# MatrixLED_v2_SCH.net
KiCad netlist of a schematic drawn in Altium Designer
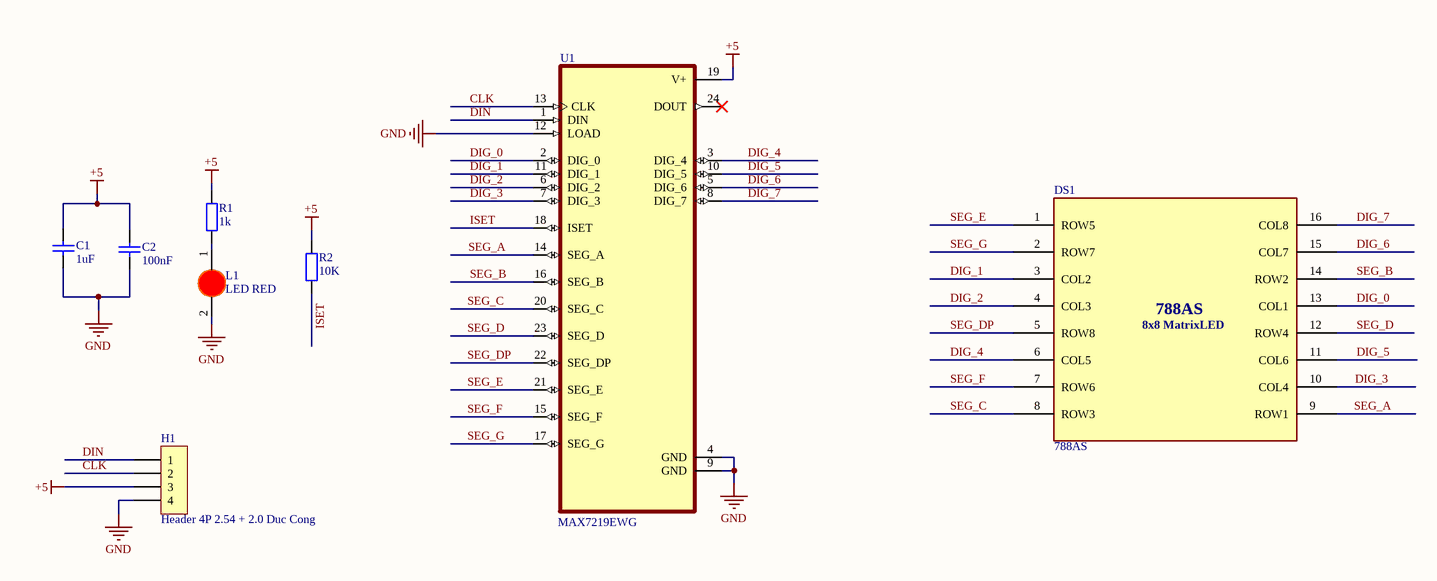
[diagram p0: MatrixLED_v2_SCH.SchDoc]

(export (version "E")
  (design (tool "Eeschema 10.0.6"))
  (components
    (comp (ref "C1")
      (value "1uF")
      (footprint "tu 0603")
      (description "Dán")
      (libsource (lib "namnt_Lib") (part "Tu 0603 104 50V 10%"))
    )
    (comp (ref "C2")
      (value "100nF")
      (footprint "tu 0603")
      (description "Dán")
      (libsource (lib "namnt_Lib") (part "Tu 0603 104 50V 10%"))
    )
    (comp (ref "DS1")
      (value "788AS")
      (footprint "788AS")
      (description "31.70mm (1.2â€) 3.0x3.0 SQUARE dot matrix LED display.BI-COLOR")
      (fields (field (name "MF") "Betlux") (field (name "MP") "BL-M12A883-DUG"))
      (libsource (lib "namnt_Lib") (part "788AS"))
    )
    (comp (ref "H1")
      (value "Header 4P 2.54 + 2.0 Duc Cong")
      (footprint "Header 4P DC 2.54 + 2.0")
      (description "Cắm")
      (libsource (lib "namnt_Lib") (part "Header 4P 2.54 + 2.0 Duc Cong"))
    )
    (comp (ref "L1")
      (value "LED RED")
      (footprint "LED-0805-Red")
      (description "Dán")
      (libsource (lib "namnt_Lib") (part "LED 0805 Do"))
    )
    (comp (ref "R1")
      (value "1k")
      (footprint "tro smd 0603")
      (description "Dán")
      (libsource (lib "namnt_Lib") (part "Tro 0603 1% 1k"))
    )
    (comp (ref "R2")
      (value "10K")
      (footprint "tro smd 0603")
      (description "Dán")
      (libsource (lib "namnt_Lib") (part "Tro 0603 1% 10k"))
    )
    (comp (ref "U1")
      (value "MAX7219EWG")
      (footprint "SOIC127P1032X265-24N")
      (description "LED Driver 64 Segment 330000uA Supply Current 24-Pin SOIC W Tube")
      (fields (field (name "MF") "Analog Devices") (field (name "MP") "MAX7219EWG+"))
      (libsource (lib "namnt_Lib") (part "MAX7219EWG"))
    )
  )
  (nets
    (net (code "1") (name "+5") (class "Default")
      (node (ref "C1") (pin "1") (pinfunction "1_1") (pintype "passive"))
      (node (ref "C2") (pin "1") (pinfunction "1_1") (pintype "passive"))
      (node (ref "H1") (pin "3") (pinfunction "3_3") (pintype "passive"))
      (node (ref "R1") (pin "2") (pinfunction "2_2") (pintype "passive"))
      (node (ref "R2") (pin "2") (pinfunction "2_2") (pintype "passive"))
      (node (ref "U1") (pin "19") (pinfunction "V+_19") (pintype "power_in"))
    )
    (net (code "2") (name "/CLK") (class "Default")
      (node (ref "H1") (pin "2") (pinfunction "2_2") (pintype "passive"))
      (node (ref "U1") (pin "13") (pinfunction "CLK_13") (pintype "input"))
    )
    (net (code "3") (name "/DIG_0") (class "Default")
      (node (ref "DS1") (pin "13") (pinfunction "COL1_13") (pintype "passive"))
      (node (ref "U1") (pin "2") (pinfunction "DIG_0_2") (pintype "bidirectional"))
    )
    (net (code "4") (name "/DIG_1") (class "Default")
      (node (ref "DS1") (pin "3") (pinfunction "COL2_3") (pintype "passive"))
      (node (ref "U1") (pin "11") (pinfunction "DIG_1_11") (pintype "bidirectional"))
    )
    (net (code "5") (name "/DIG_2") (class "Default")
      (node (ref "DS1") (pin "4") (pinfunction "COL3_4") (pintype "passive"))
      (node (ref "U1") (pin "6") (pinfunction "DIG_2_6") (pintype "bidirectional"))
    )
    (net (code "6") (name "/DIG_3") (class "Default")
      (node (ref "DS1") (pin "10") (pinfunction "COL4_10") (pintype "passive"))
      (node (ref "U1") (pin "7") (pinfunction "DIG_3_7") (pintype "bidirectional"))
    )
    (net (code "7") (name "/DIG_4") (class "Default")
      (node (ref "DS1") (pin "6") (pinfunction "COL5_6") (pintype "passive"))
      (node (ref "U1") (pin "3") (pinfunction "DIG_4_3") (pintype "bidirectional"))
    )
    (net (code "8") (name "/DIG_5") (class "Default")
      (node (ref "DS1") (pin "11") (pinfunction "COL6_11") (pintype "passive"))
      (node (ref "U1") (pin "10") (pinfunction "DIG_5_10") (pintype "bidirectional"))
    )
    (net (code "9") (name "/DIG_6") (class "Default")
      (node (ref "DS1") (pin "15") (pinfunction "COL7_15") (pintype "passive"))
      (node (ref "U1") (pin "5") (pinfunction "DIG_6_5") (pintype "bidirectional"))
    )
    (net (code "10") (name "/DIG_7") (class "Default")
      (node (ref "DS1") (pin "16") (pinfunction "COL8_16") (pintype "passive"))
      (node (ref "U1") (pin "8") (pinfunction "DIG_7_8") (pintype "bidirectional"))
    )
    (net (code "11") (name "/DIN") (class "Default")
      (node (ref "H1") (pin "1") (pinfunction "1_1") (pintype "passive"))
      (node (ref "U1") (pin "1") (pinfunction "DIN_1") (pintype "input"))
    )
    (net (code "12") (name "/ISET") (class "Default")
      (node (ref "R2") (pin "1") (pinfunction "1_1") (pintype "passive"))
      (node (ref "U1") (pin "18") (pinfunction "ISET_18") (pintype "bidirectional"))
    )
    (net (code "13") (name "/SEG_A") (class "Default")
      (node (ref "DS1") (pin "9") (pinfunction "ROW1_9") (pintype "passive"))
      (node (ref "U1") (pin "14") (pinfunction "SEG_A_14") (pintype "bidirectional"))
    )
    (net (code "14") (name "/SEG_B") (class "Default")
      (node (ref "DS1") (pin "14") (pinfunction "ROW2_14") (pintype "passive"))
      (node (ref "U1") (pin "16") (pinfunction "SEG_B_16") (pintype "bidirectional"))
    )
    (net (code "15") (name "/SEG_C") (class "Default")
      (node (ref "DS1") (pin "8") (pinfunction "ROW3_8") (pintype "passive"))
      (node (ref "U1") (pin "20") (pinfunction "SEG_C_20") (pintype "bidirectional"))
    )
    (net (code "16") (name "/SEG_D") (class "Default")
      (node (ref "DS1") (pin "12") (pinfunction "ROW4_12") (pintype "passive"))
      (node (ref "U1") (pin "23") (pinfunction "SEG_D_23") (pintype "bidirectional"))
    )
    (net (code "17") (name "/SEG_DP") (class "Default")
      (node (ref "DS1") (pin "5") (pinfunction "ROW8_5") (pintype "passive"))
      (node (ref "U1") (pin "22") (pinfunction "SEG_DP_22") (pintype "bidirectional"))
    )
    (net (code "18") (name "/SEG_E") (class "Default")
      (node (ref "DS1") (pin "1") (pinfunction "ROW5_1") (pintype "passive"))
      (node (ref "U1") (pin "21") (pinfunction "SEG_E_21") (pintype "bidirectional"))
    )
    (net (code "19") (name "/SEG_F") (class "Default")
      (node (ref "DS1") (pin "7") (pinfunction "ROW6_7") (pintype "passive"))
      (node (ref "U1") (pin "15") (pinfunction "SEG_F_15") (pintype "bidirectional"))
    )
    (net (code "20") (name "/SEG_G") (class "Default")
      (node (ref "DS1") (pin "2") (pinfunction "ROW7_2") (pintype "passive"))
      (node (ref "U1") (pin "17") (pinfunction "SEG_G_17") (pintype "bidirectional"))
    )
    (net (code "21") (name "GND") (class "Default")
      (node (ref "C1") (pin "2") (pinfunction "2_2") (pintype "passive"))
      (node (ref "C2") (pin "2") (pinfunction "2_2") (pintype "passive"))
      (node (ref "H1") (pin "4") (pinfunction "4_4") (pintype "passive"))
      (node (ref "L1") (pin "2") (pinfunction "K_2") (pintype "passive"))
      (node (ref "U1") (pin "12") (pinfunction "LOAD_12") (pintype "input"))
      (node (ref "U1") (pin "4") (pinfunction "GND_4") (pintype "power_in"))
      (node (ref "U1") (pin "9") (pinfunction "GND_9") (pintype "power_in"))
    )
    (net (code "22") (name "Net-(L1-A)") (class "Default")
      (node (ref "L1") (pin "1") (pinfunction "A_1") (pintype "passive"))
      (node (ref "R1") (pin "1") (pinfunction "1_1") (pintype "passive"))
    )
    (net (code "23") (name "unconnected-(U1-DOUT-Pad24)") (class "Default")
      (node (ref "U1") (pin "24") (pinfunction "DOUT_24") (pintype "output+no_connect"))
    )
  )
)
